# PL2812B.net
KiCad netlist of a schematic drawn in Altium Designer
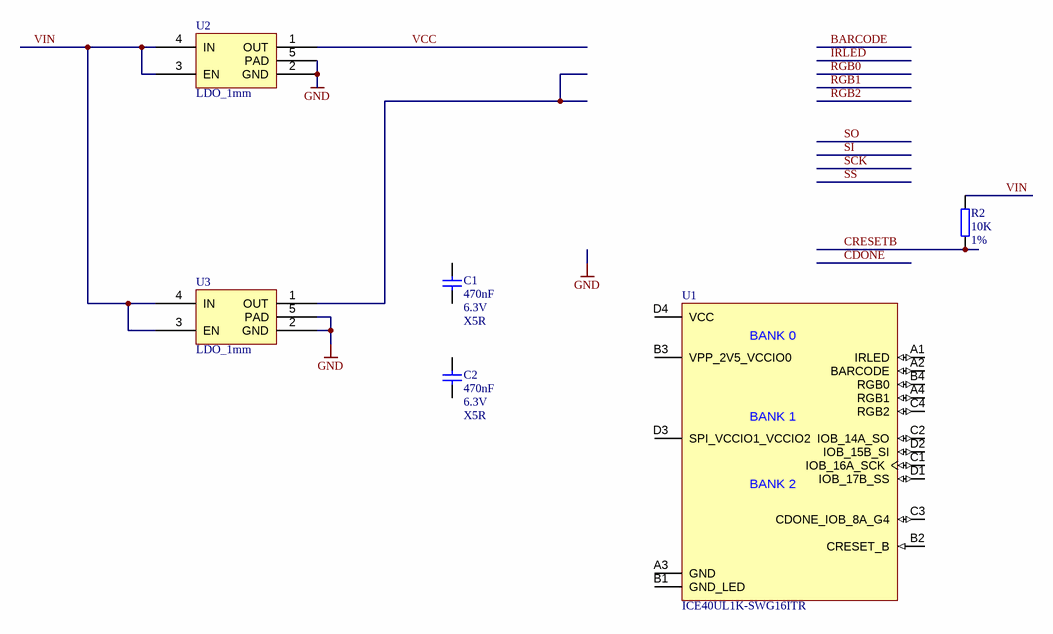
[diagram p0: PL2812B.SchDoc]

(export (version "E")
  (design (tool "Eeschema 10.0.6"))
  (components
    (comp (ref "C1")
      (value "470nF")
      (footprint "CAPC0603X33N")
      (description "KON 470nF X5R 6.3V SMD 20%")
      (fields
        (field (name "VOLTAGE") "6.3V")
        (field (name "TECHNOLOGY") "X5R")
        (field (name "TOLERANCE") "20%")
      )
      (libsource (lib "TE") (part "CAP-NP"))
    )
    (comp (ref "C2")
      (value "470nF")
      (footprint "CAPC0603X33N")
      (description "KON 470nF X5R 6.3V SMD 20%")
      (fields
        (field (name "VOLTAGE") "6.3V")
        (field (name "TECHNOLOGY") "X5R")
        (field (name "TOLERANCE") "20%")
      )
      (libsource (lib "TE") (part "CAP-NP"))
    )
    (comp (ref "R2")
      (value "10K")
      (footprint "RESC0603X26N")
      (description "WID SMD 10K 1% 0,05W")
      (fields (field (name "TOLERANCE") "1%"))
      (libsource (lib "TE") (part "RES"))
    )
    (comp (ref "U1")
      (value "ICE40UL1K-SWG16ITR")
      (footprint "BGA16C35P4X4_140X140X49B21N")
      (libsource (lib "altium-import") (part "root_0_ICE40UL1K-SWG16ITR_"))
    )
    (comp (ref "U2")
      (value "LDO_1mm")
      (footprint "DFN65P100X45-4N")
      (libsource (lib "Schlib1") (part "LDO_1mm"))
    )
    (comp (ref "U3")
      (value "LDO_1mm")
      (footprint "DFN65P100X45-4N")
      (libsource (lib "Schlib1") (part "LDO_1mm"))
    )
  )
  (nets
    (net (code "3") (name "/CRESETB") (class "Default")
      (node (ref "R2") (pin "2") (pinfunction "2_2") (pintype "passive"))
    )
    (net (code "12") (name "/VCC") (class "Default")
      (node (ref "U2") (pin "1") (pinfunction "OUT_1") (pintype "passive"))
    )
    (net (code "13") (name "/VIN") (class "Default")
      (node (ref "R2") (pin "1") (pinfunction "1_1") (pintype "passive"))
      (node (ref "U2") (pin "3") (pinfunction "EN_3") (pintype "passive"))
      (node (ref "U2") (pin "4") (pinfunction "IN_4") (pintype "passive"))
      (node (ref "U3") (pin "3") (pinfunction "EN_3") (pintype "passive"))
      (node (ref "U3") (pin "4") (pinfunction "IN_4") (pintype "passive"))
    )
    (net (code "14") (name "GND") (class "Default")
      (node (ref "U2") (pin "2") (pinfunction "GND_2") (pintype "passive"))
      (node (ref "U2") (pin "5") (pinfunction "PAD_5") (pintype "passive"))
      (node (ref "U3") (pin "2") (pinfunction "GND_2") (pintype "passive"))
      (node (ref "U3") (pin "5") (pinfunction "PAD_5") (pintype "passive"))
    )
    (net (code "15") (name "unconnected-(C1-Pad1)") (class "Default")
      (node (ref "C1") (pin "1") (pinfunction "1_1") (pintype "passive"))
    )
    (net (code "16") (name "unconnected-(C1-Pad2)") (class "Default")
      (node (ref "C1") (pin "2") (pinfunction "2_2") (pintype "passive"))
    )
    (net (code "17") (name "unconnected-(C2-Pad1)") (class "Default")
      (node (ref "C2") (pin "1") (pinfunction "1_1") (pintype "passive"))
    )
    (net (code "18") (name "unconnected-(C2-Pad2)") (class "Default")
      (node (ref "C2") (pin "2") (pinfunction "2_2") (pintype "passive"))
    )
    (net (code "19") (name "unconnected-(U1-BARCODE-PadA2)") (class "Default")
      (node (ref "U1") (pin "A2") (pinfunction "BARCODE_A2") (pintype "bidirectional"))
    )
    (net (code "20") (name "unconnected-(U1-CDONE_IOB_8A_G4-PadC3)") (class "Default")
      (node (ref "U1") (pin "C3") (pinfunction "CDONE_IOB_8A_G4_C3") (pintype "bidirectional"))
    )
    (net (code "21") (name "unconnected-(U1-CRESET_B-PadB2)") (class "Default")
      (node (ref "U1") (pin "B2") (pinfunction "CRESET_B_B2") (pintype "input"))
    )
    (net (code "22") (name "unconnected-(U1-GND-PadA3)") (class "Default")
      (node (ref "U1") (pin "A3") (pinfunction "GND_A3") (pintype "power_in"))
    )
    (net (code "23") (name "unconnected-(U1-GND_LED-PadB1)") (class "Default")
      (node (ref "U1") (pin "B1") (pinfunction "GND_LED_B1") (pintype "power_in"))
    )
    (net (code "24") (name "unconnected-(U1-IOB_14A_SO-PadC2)") (class "Default")
      (node (ref "U1") (pin "C2") (pinfunction "IOB_14A_SO_C2") (pintype "bidirectional"))
    )
    (net (code "25") (name "unconnected-(U1-IOB_15B_SI-PadD2)") (class "Default")
      (node (ref "U1") (pin "D2") (pinfunction "IOB_15B_SI_D2") (pintype "bidirectional"))
    )
    (net (code "26") (name "unconnected-(U1-IOB_16A_SCK-PadC1)") (class "Default")
      (node (ref "U1") (pin "C1") (pinfunction "IOB_16A_SCK_C1") (pintype "bidirectional"))
    )
    (net (code "27") (name "unconnected-(U1-IOB_17B_SS-PadD1)") (class "Default")
      (node (ref "U1") (pin "D1") (pinfunction "IOB_17B_SS_D1") (pintype "bidirectional"))
    )
    (net (code "28") (name "unconnected-(U1-IRLED-PadA1)") (class "Default")
      (node (ref "U1") (pin "A1") (pinfunction "IRLED_A1") (pintype "bidirectional"))
    )
    (net (code "29") (name "unconnected-(U1-RGB0-PadB4)") (class "Default")
      (node (ref "U1") (pin "B4") (pinfunction "RGB0_B4") (pintype "bidirectional"))
    )
    (net (code "30") (name "unconnected-(U1-RGB1-PadA4)") (class "Default")
      (node (ref "U1") (pin "A4") (pinfunction "RGB1_A4") (pintype "bidirectional"))
    )
    (net (code "31") (name "unconnected-(U1-RGB2-PadC4)") (class "Default")
      (node (ref "U1") (pin "C4") (pinfunction "RGB2_C4") (pintype "bidirectional"))
    )
    (net (code "32") (name "unconnected-(U1-SPI_VCCIO1_VCCIO2-PadD3)") (class "Default")
      (node (ref "U1") (pin "D3") (pinfunction "SPI_VCCIO1_VCCIO2_D3") (pintype "power_in"))
    )
    (net (code "33") (name "unconnected-(U1-VCC-PadD4)") (class "Default")
      (node (ref "U1") (pin "D4") (pinfunction "VCC_D4") (pintype "power_in"))
    )
    (net (code "34") (name "unconnected-(U1-VPP_2V5_VCCIO0-PadB3)") (class "Default")
      (node (ref "U1") (pin "B3") (pinfunction "VPP_2V5_VCCIO0_B3") (pintype "power_in"))
    )
    (net (code "35") (name "unconnected-(U3-OUT-Pad1)") (class "Default")
      (node (ref "U3") (pin "1") (pinfunction "OUT_1") (pintype "passive"))
    )
  )
)
